# Fourier.net
KiCad netlist of a schematic drawn in Altium Designer
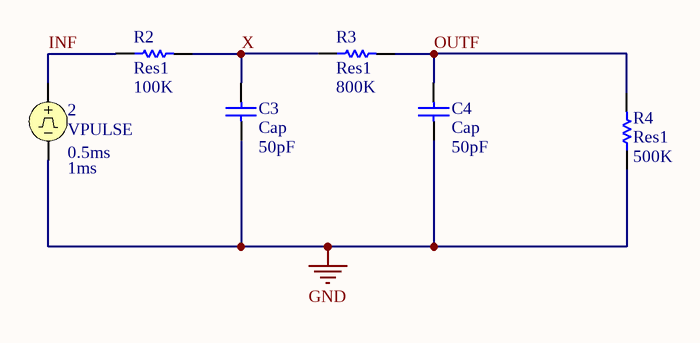
[diagram p0: Fourier.SchDoc]

(export (version "E")
  (design (tool "Eeschema 10.0.6"))
  (components
    (comp (ref "2")
      (value "VPULSE")
      (description "Pulse Voltage Source")
      (fields
        (field (name "PULSE WIDTH") "0.5ms")
        (field (name "PERIOD") "1ms")
        (field (name "PUBLISHER") "Altium Limited")
      )
      (libsource (lib "Simulation Sources") (part "VPULSE"))
    )
    (comp (ref "C3")
      (value "Cap")
      (footprint "RAD-0.3")
      (description "Capacitor")
      (fields (field (name "ALTIUM_VALUE") "50pF") (field (name "PUBLISHER") "Altium Limited"))
      (libsource (lib "Miscellaneous Devices") (part "Cap"))
    )
    (comp (ref "C4")
      (value "Cap")
      (footprint "RAD-0.3")
      (description "Capacitor")
      (fields (field (name "ALTIUM_VALUE") "50pF") (field (name "PUBLISHER") "Altium Limited"))
      (libsource (lib "Miscellaneous Devices") (part "Cap"))
    )
    (comp (ref "R2")
      (value "Res1")
      (footprint "AXIAL-0.3")
      (description "Resistor")
      (fields (field (name "ALTIUM_VALUE") "100K") (field (name "PUBLISHER") "Altium Limited"))
      (libsource (lib "Miscellaneous Devices") (part "Res1"))
    )
    (comp (ref "R3")
      (value "Res1")
      (footprint "AXIAL-0.3")
      (description "Resistor")
      (fields (field (name "ALTIUM_VALUE") "800K") (field (name "PUBLISHER") "Altium Limited"))
      (libsource (lib "Miscellaneous Devices") (part "Res1"))
    )
    (comp (ref "R4")
      (value "Res1")
      (footprint "AXIAL-0.3")
      (description "Resistor")
      (fields (field (name "ALTIUM_VALUE") "500K") (field (name "PUBLISHER") "Altium Limited"))
      (libsource (lib "Miscellaneous Devices") (part "Res1"))
    )
  )
  (nets
    (net (code "1") (name "/INF") (class "Default")
      (node (ref "2") (pin "1") (pinfunction "1_1") (pintype "passive"))
      (node (ref "R2") (pin "1") (pinfunction "1_1") (pintype "passive"))
    )
    (net (code "2") (name "/OUTF") (class "Default")
      (node (ref "C4") (pin "2") (pinfunction "2_2") (pintype "passive"))
      (node (ref "R3") (pin "2") (pinfunction "2_2") (pintype "passive"))
      (node (ref "R4") (pin "2") (pinfunction "2_2") (pintype "passive"))
    )
    (net (code "3") (name "/X") (class "Default")
      (node (ref "C3") (pin "2") (pinfunction "2_2") (pintype "passive"))
      (node (ref "R2") (pin "2") (pinfunction "2_2") (pintype "passive"))
      (node (ref "R3") (pin "1") (pinfunction "1_1") (pintype "passive"))
    )
    (net (code "4") (name "GND") (class "Default")
      (node (ref "2") (pin "2") (pinfunction "2_2") (pintype "passive"))
      (node (ref "C3") (pin "1") (pinfunction "1_1") (pintype "passive"))
      (node (ref "C4") (pin "1") (pinfunction "1_1") (pintype "passive"))
      (node (ref "R4") (pin "1") (pinfunction "1_1") (pintype "passive"))
    )
  )
)
